# Headers.net
KiCad netlist of a schematic drawn in Altium Designer
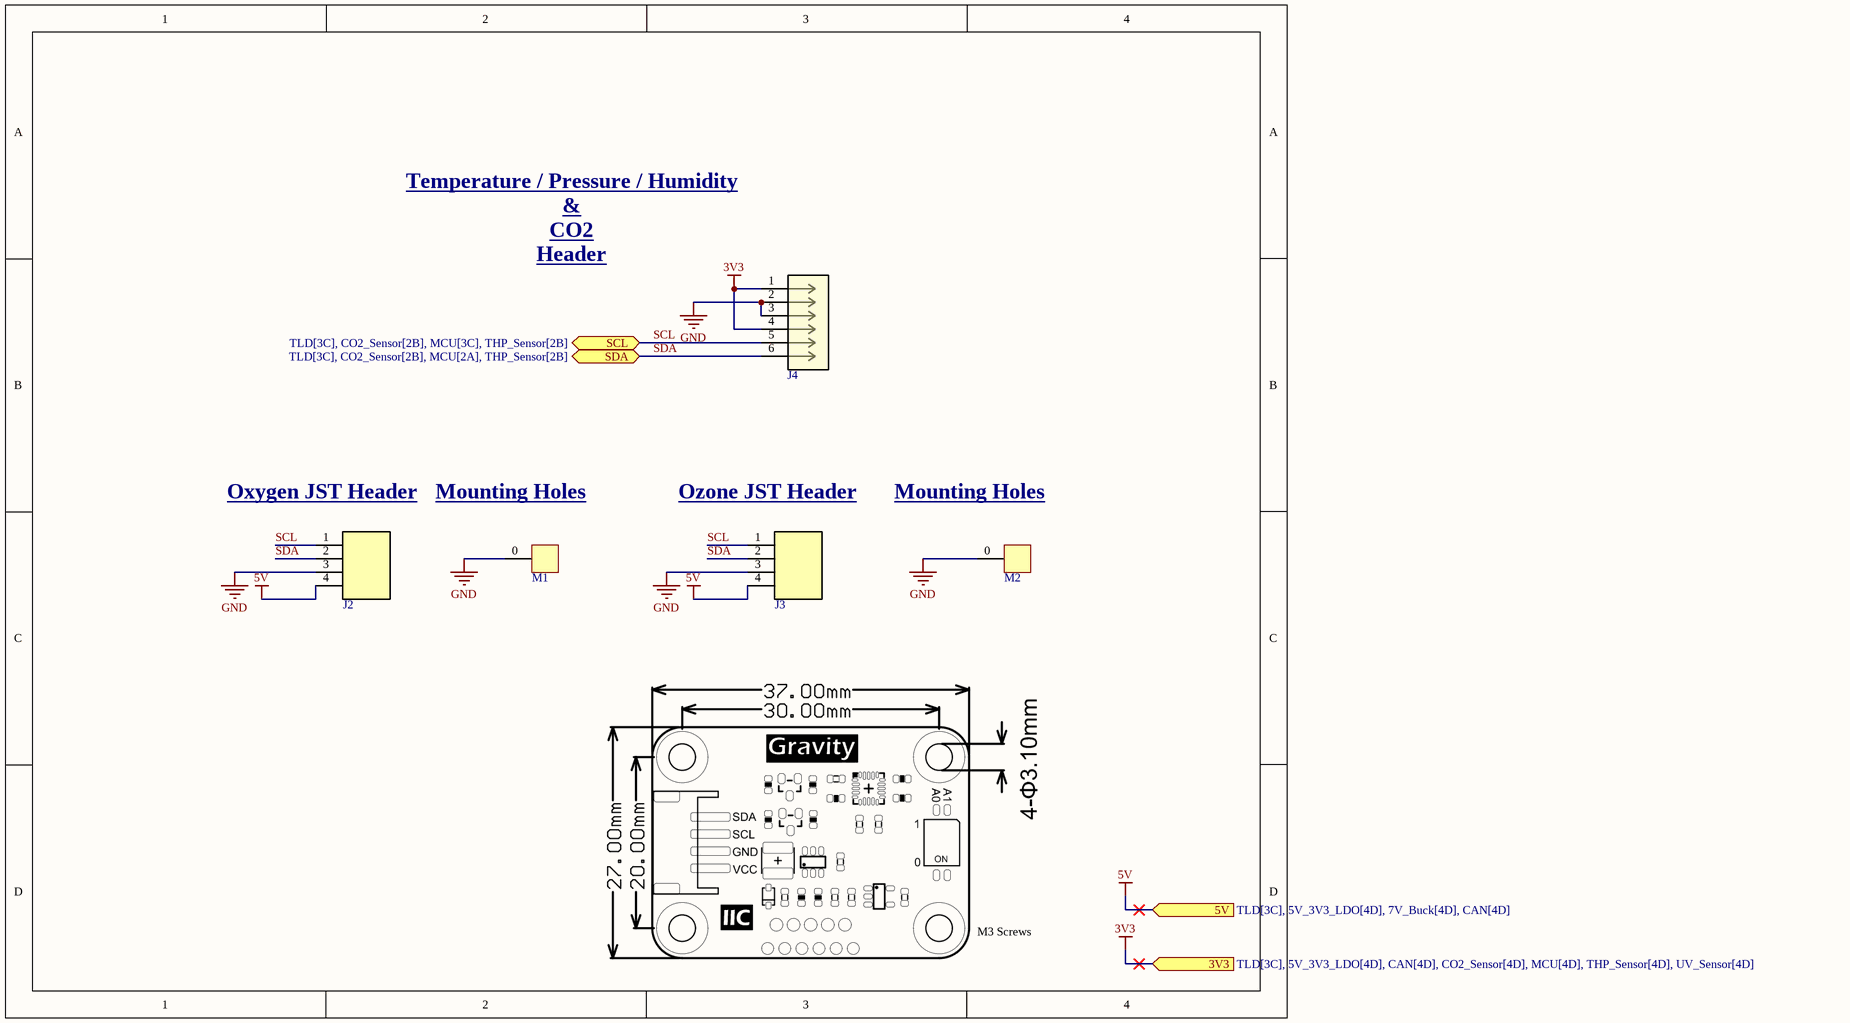
[diagram p0: Headers.SchDoc]

(export (version "E")
  (design (tool "Eeschema 10.0.6"))
  (components
    (comp (ref "J2")
      (value "S4B-PH-SM4-TB")
      (footprint "JST_S4B-PH-SM4-TB")
      (description "Connector Header Surface Mount, Right Angle 4 position 0.079 (2.00mm)")
      (fields (field (name "MF") "JST Sales"))
      (libsource (lib "JLC_25") (part "CONN-4POS-JST-0001"))
    )
    (comp (ref "J3")
      (value "S4B-PH-SM4-TB")
      (footprint "JST_S4B-PH-SM4-TB")
      (description "Connector Header Surface Mount, Right Angle 4 position 0.079 (2.00mm)")
      (fields (field (name "MF") "JST Sales"))
      (libsource (lib "JLC_25") (part "CONN-4POS-JST-0001"))
    )
    (comp (ref "J4")
      (value "430450600")
      (footprint "CONN_SD-43045-001_06_MOL")
      (fields (field (name "COPYRIGHT") "Copyright (C) 2025 Ultra Librarian. All rights reserved."))
      (libsource (lib "Molex Microfit") (part "CONN_6POS_430450600"))
    )
    (comp (ref "M1")
      (value "DK-Oxygen")
      (footprint "DK-Oxygen")
      (libsource (lib "JLC_25") (part "DK-Oxygen"))
    )
    (comp (ref "M2") (value "DK-Ozone") (footprint "DK-Ozone") (libsource (lib "JLC_25") (part "DK-Ozone")))
  )
  (nets
    (net (code "1") (name "/SCL") (class "Default")
      (node (ref "J2") (pin "1") (pinfunction "1_1") (pintype "passive"))
      (node (ref "J3") (pin "1") (pinfunction "1_1") (pintype "passive"))
      (node (ref "J4") (pin "5") (pinfunction "5_5") (pintype "passive"))
    )
    (net (code "2") (name "/SDA") (class "Default")
      (node (ref "J2") (pin "2") (pinfunction "2_2") (pintype "passive"))
      (node (ref "J3") (pin "2") (pinfunction "2_2") (pintype "passive"))
      (node (ref "J4") (pin "6") (pinfunction "6_6") (pintype "passive"))
    )
    (net (code "3") (name "3V3") (class "Default")
      (node (ref "J4") (pin "1") (pinfunction "1_1") (pintype "passive"))
      (node (ref "J4") (pin "4") (pinfunction "4_4") (pintype "passive"))
    )
    (net (code "4") (name "5V") (class "Default")
      (node (ref "J2") (pin "4") (pinfunction "4_4") (pintype "passive"))
      (node (ref "J3") (pin "4") (pinfunction "4_4") (pintype "passive"))
    )
    (net (code "5") (name "GND") (class "Default")
      (node (ref "J2") (pin "3") (pinfunction "3_3") (pintype "passive"))
      (node (ref "J3") (pin "3") (pinfunction "3_3") (pintype "passive"))
      (node (ref "J4") (pin "2") (pinfunction "2_2") (pintype "passive"))
      (node (ref "J4") (pin "3") (pinfunction "3_3") (pintype "passive"))
      (node (ref "M1") (pin "0") (pinfunction "0_0") (pintype "passive"))
      (node (ref "M2") (pin "0") (pinfunction "0_0") (pintype "passive"))
    )
  )
)
